# Oscillator.net
KiCad netlist of a schematic drawn in Altium Designer
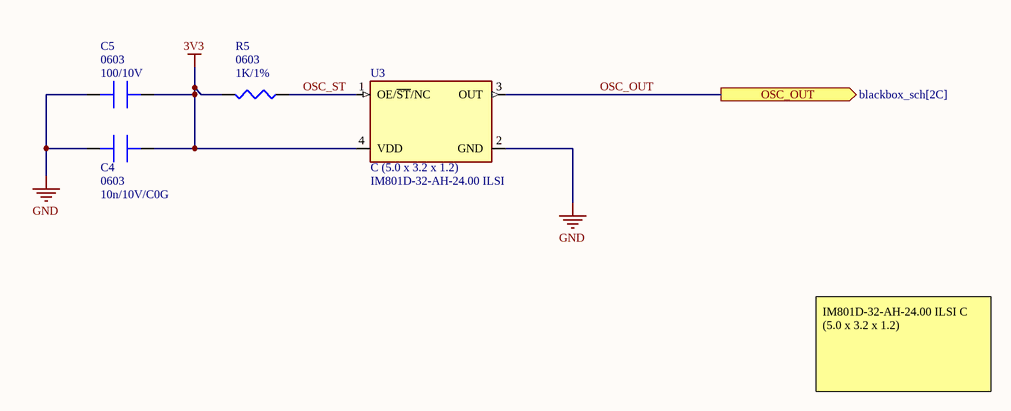
[diagram p0: Oscillator.SchDoc]

(export (version "E")
  (design (tool "Eeschema 10.0.6"))
  (components
    (comp (ref "C4")
      (value "10n/10V/C0G")
      (footprint "CAPC1608X10L [0603]")
      (description "Standard capacitor")
      (fields (field (name "PACKAGE") "0603") (field (name "Comment") "C"))
      (libsource (lib "SR_Library") (part "C"))
    )
    (comp (ref "C5")
      (value "100/10V")
      (footprint "CAPC1608X10L [0603]")
      (description "Standard capacitor")
      (fields (field (name "PACKAGE") "0603") (field (name "Comment") "C"))
      (libsource (lib "SR_Library") (part "C"))
    )
    (comp (ref "R5")
      (value "1K/1%")
      (footprint "RESC1608X05L [0603]")
      (description "Standard resistor")
      (fields (field (name "PACKAGE") "0603") (field (name "Comment") "R"))
      (libsource (lib "SR_Library") (part "R"))
    )
    (comp (ref "U3")
      (value "IM801x-xx-xx-xx.xxx")
      (footprint "IM801C")
      (description "MEMS oscillator, low power, LVCMOS")
      (fields (field (name "PACKAGE") "C (5.0 x 3.2 x 1.2)") (field (name "PN") "IM801D-32-AH-24.00 ILSI"))
      (libsource (lib "_IC_Time") (part "IM801x-xx-xx-xx.xxx"))
    )
  )
  (nets
    (net (code "1") (name "/OSC_OUT") (class "Default")
      (node (ref "U3") (pin "3") (pinfunction "OUT_3") (pintype "output"))
    )
    (net (code "2") (name "/OSC_ST") (class "Default")
      (node (ref "R5") (pin "2") (pinfunction "2_2") (pintype "passive"))
      (node (ref "U3") (pin "1") (pinfunction "OE/~{ST}/NC_1") (pintype "input"))
    )
    (net (code "3") (name "3V3") (class "Default")
      (node (ref "C4") (pin "2") (pinfunction "2_2") (pintype "passive"))
      (node (ref "C5") (pin "2") (pinfunction "2_2") (pintype "passive"))
      (node (ref "R5") (pin "1") (pinfunction "1_1") (pintype "passive"))
      (node (ref "U3") (pin "4") (pinfunction "VDD_4") (pintype "power_in"))
    )
    (net (code "4") (name "GND") (class "Default")
      (node (ref "C4") (pin "1") (pinfunction "1_1") (pintype "passive"))
      (node (ref "C5") (pin "1") (pinfunction "1_1") (pintype "passive"))
      (node (ref "U3") (pin "2") (pinfunction "GND_2") (pintype "power_in"))
    )
  )
)
